# bela_expansion_card_3.net
KiCad netlist of a schematic drawn in Altium Designer
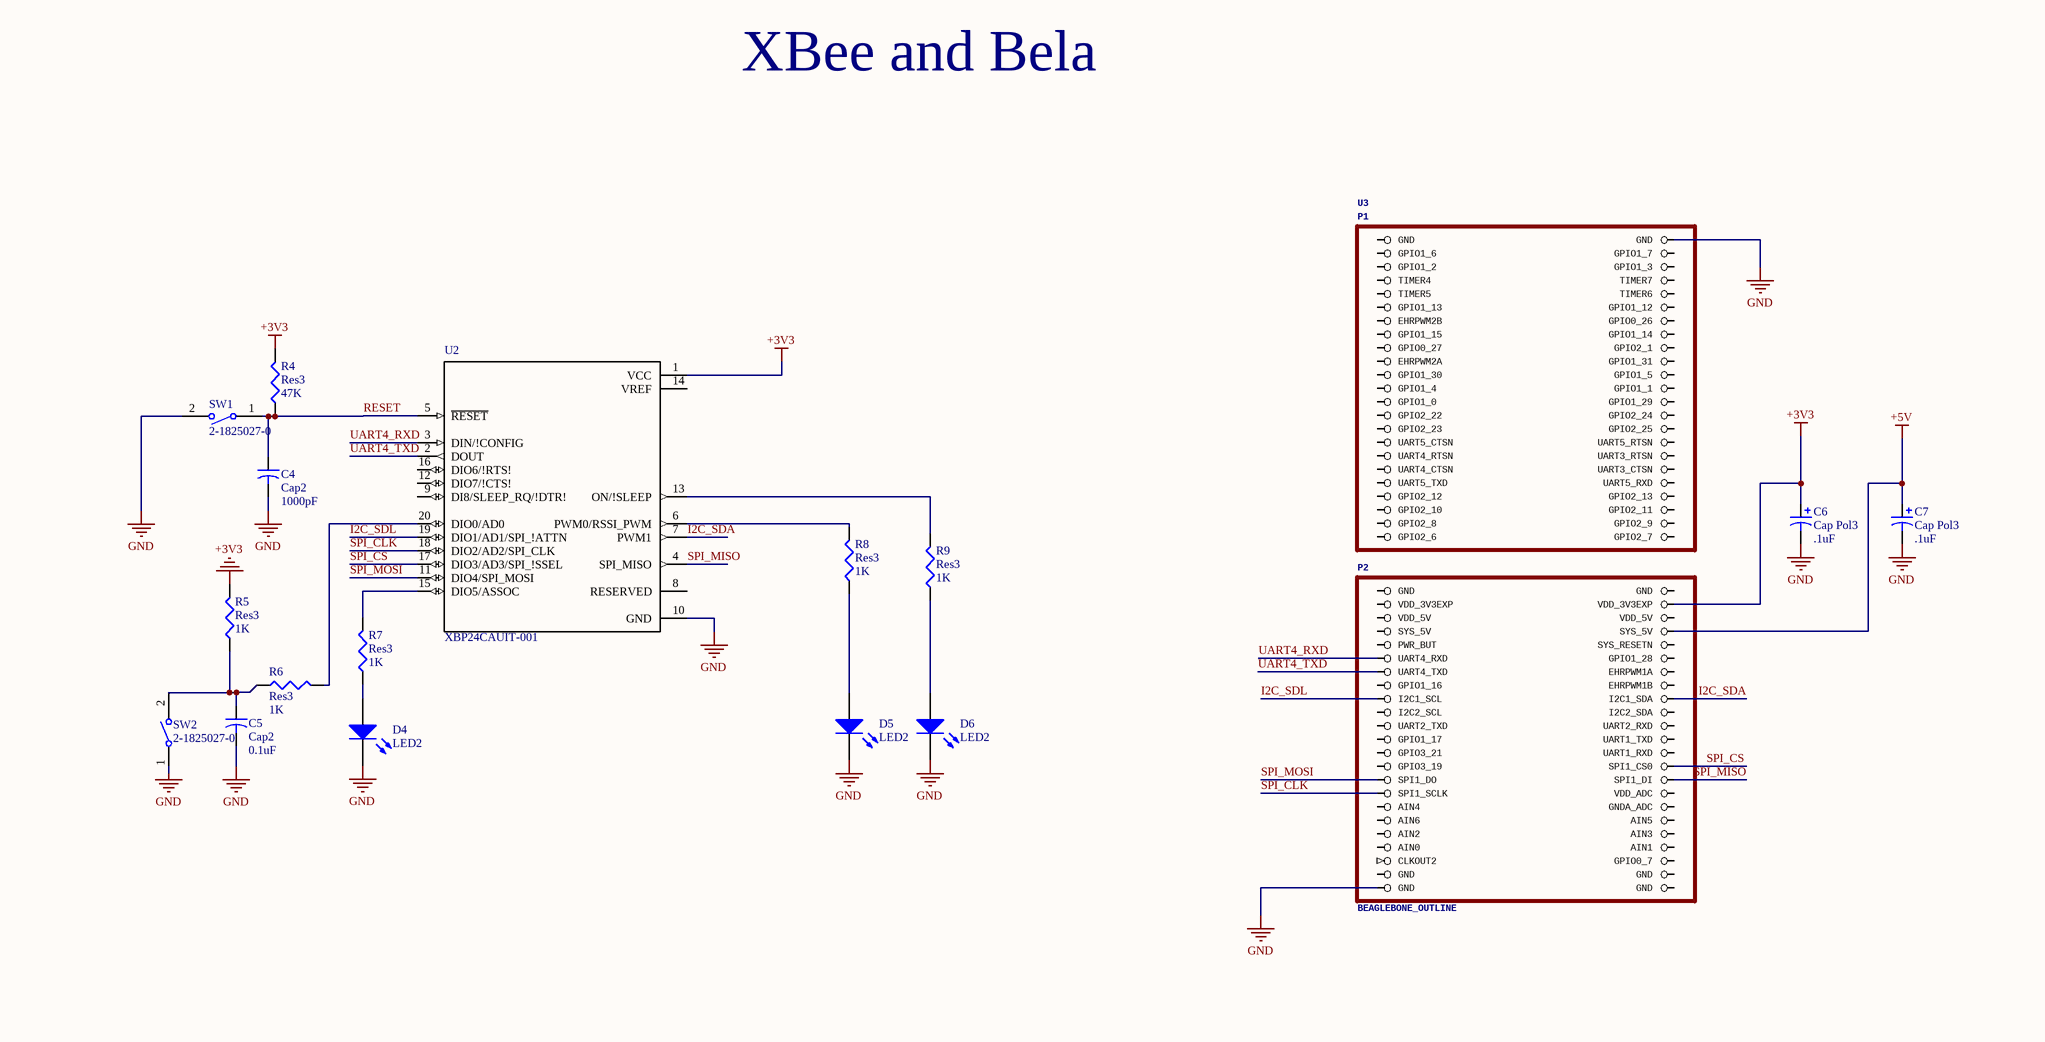
[diagram p0: bela_expansion_card_3.SchDoc]

(export (version "E")
  (design (tool "Eeschema 10.0.6"))
  (components
    (comp (ref "C4")
      (value "Cap2")
      (footprint "C0805")
      (description "Capacitor")
      (fields (field (name "ALTIUM_VALUE") "1000pF") (field (name "PUBLISHER") "Altium Limited"))
      (libsource (lib "EE_Emerge_SkillsProject") (part "Cap2_4"))
    )
    (comp (ref "C5")
      (value "Cap2")
      (footprint "C0805")
      (description "Capacitor")
      (fields (field (name "ALTIUM_VALUE") "0.1uF") (field (name "PUBLISHER") "Altium Limited"))
      (libsource (lib "EE_Emerge_SkillsProject") (part "Cap2_1"))
    )
    (comp (ref "C6")
      (value "Cap Pol3")
      (footprint "C0805")
      (description "Polarized Capacitor (Surface Mount)")
      (fields (field (name "ALTIUM_VALUE") ".1uF") (field (name "PUBLISHER") "Altium Limited"))
      (libsource (lib "Miscellaneous Devices") (part "Cap Pol3"))
    )
    (comp (ref "C7")
      (value "Cap Pol3")
      (footprint "C0805")
      (description "Polarized Capacitor (Surface Mount)")
      (fields (field (name "ALTIUM_VALUE") ".1uF") (field (name "PUBLISHER") "Altium Limited"))
      (libsource (lib "Miscellaneous Devices") (part "Cap Pol3"))
    )
    (comp (ref "D4")
      (value "LED2")
      (footprint "3.2X1.6X1.1")
      (description "Typical RED, GREEN, YELLOW, AMBER GaAs LED")
      (fields (field (name "PUBLISHER") "Altium Limited"))
      (libsource (lib "Miscellaneous Devices") (part "LED2"))
    )
    (comp (ref "D5")
      (value "LED2")
      (footprint "3.2X1.6X1.1")
      (description "Typical RED, GREEN, YELLOW, AMBER GaAs LED")
      (fields (field (name "PUBLISHER") "Altium Limited"))
      (libsource (lib "Miscellaneous Devices") (part "LED2"))
    )
    (comp (ref "D6")
      (value "LED2")
      (footprint "3.2X1.6X1.1")
      (description "Typical RED, GREEN, YELLOW, AMBER GaAs LED")
      (fields (field (name "PUBLISHER") "Altium Limited"))
      (libsource (lib "Miscellaneous Devices") (part "LED2"))
    )
    (comp (ref "R4")
      (value "Res3")
      (footprint "6-0805_L")
      (description "Resistor")
      (fields (field (name "ALTIUM_VALUE") "47K") (field (name "PUBLISHER") "Altium Limited"))
      (libsource (lib "Miscellaneous Devices") (part "Res3"))
    )
    (comp (ref "R5")
      (value "Res3")
      (footprint "6-0805_L")
      (description "Resistor")
      (fields (field (name "ALTIUM_VALUE") "1K") (field (name "PUBLISHER") "Altium Limited"))
      (libsource (lib "Miscellaneous Devices") (part "Res3"))
    )
    (comp (ref "R6")
      (value "Res3")
      (footprint "6-0805_L")
      (description "Resistor")
      (fields (field (name "ALTIUM_VALUE") "1K") (field (name "PUBLISHER") "Altium Limited"))
      (libsource (lib "Miscellaneous Devices") (part "Res3"))
    )
    (comp (ref "R7")
      (value "Res3")
      (footprint "6-0805_L")
      (description "Resistor")
      (fields (field (name "ALTIUM_VALUE") "1K") (field (name "PUBLISHER") "Altium Limited"))
      (libsource (lib "Miscellaneous Devices") (part "Res3"))
    )
    (comp (ref "R8")
      (value "Res3")
      (footprint "6-0805_L")
      (description "Resistor")
      (fields (field (name "ALTIUM_VALUE") "1K") (field (name "PUBLISHER") "Altium Limited"))
      (libsource (lib "Miscellaneous Devices") (part "Res3"))
    )
    (comp (ref "R9")
      (value "Res3")
      (footprint "6-0805_L")
      (description "Resistor")
      (fields (field (name "ALTIUM_VALUE") "1K") (field (name "PUBLISHER") "Altium Limited"))
      (libsource (lib "Miscellaneous Devices") (part "Res3"))
    )
    (comp (ref "SW1")
      (value "2-1825027-0")
      (footprint "DPST-4")
      (description "Micro-Miniature Pushbutton Switch, 50 mA, -35 to 85 degC, 2-Pin THD, RoHS, Bulk")
      (fields (field (name "MANUFACTURER") "TE Connectivity"))
      (libsource (lib "EE_Emerge_SkillsProject") (part "CMP-2000-05529-1"))
    )
    (comp (ref "SW2")
      (value "2-1825027-0")
      (footprint "DPST-4")
      (description "Micro-Miniature Pushbutton Switch, 50 mA, -35 to 85 degC, 2-Pin THD, RoHS, Bulk")
      (fields (field (name "MANUFACTURER") "TE Connectivity"))
      (libsource (lib "EE_Emerge_SkillsProject") (part "CMP-2000-05529-1"))
    )
    (comp (ref "U2")
      (value "XBP24CAUIT-001")
      (footprint "*MODULE_XBP24CAUIT-001")
      (description "802.15.4 Transceiver Module 2.4GHz Antenna Not Included, U.FL Through Hole")
      (fields (field (name "MF") "Digi International"))
      (libsource (lib "XBP24CAUIT-001") (part "XBP24CAUIT-001"))
    )
    (comp (ref "U3")
      (value "BEAGLEBONE_OUTLINE")
      (footprint "BEAGLEBONE_SHIELD")
      (description "Should match A3 pinout - but not completely tested")
      (fields (field (name "P1") "P1") (field (name "P2") "P2"))
      (libsource (lib "adafruit") (part "BEAGLEBONE_OUTLINE"))
    )
  )
  (nets
    (net (code "1") (name "+3V3") (class "Default")
      (node (ref "C6") (pin "1") (pinfunction "1_1") (pintype "passive"))
      (node (ref "R4") (pin "2") (pinfunction "2_2") (pintype "passive"))
      (node (ref "R5") (pin "2") (pinfunction "2_2") (pintype "passive"))
      (node (ref "U2") (pin "1") (pinfunction "VCC_1") (pintype "power_in"))
      (node (ref "U3") (pin "50") (pinfunction "VDD_3V3EXP_50") (pintype "power_in"))
    )
    (net (code "2") (name "+5V") (class "Default")
      (node (ref "C7") (pin "1") (pinfunction "1_1") (pintype "passive"))
      (node (ref "U3") (pin "54") (pinfunction "SYS_5V_54") (pintype "passive"))
    )
    (net (code "3") (name "/I2C_SDA") (class "Default")
      (node (ref "U2") (pin "7") (pinfunction "PWM1_7") (pintype "output"))
      (node (ref "U3") (pin "64") (pinfunction "I2C1_SDA_64") (pintype "passive"))
    )
    (net (code "4") (name "/I2C_SDL") (class "Default")
      (node (ref "U2") (pin "19") (pinfunction "DIO1/AD1/SPI_!ATTN_19") (pintype "bidirectional"))
      (node (ref "U3") (pin "63") (pinfunction "I2C1_SCL_63") (pintype "passive"))
    )
    (net (code "5") (name "/RESET") (class "Default")
      (node (ref "C4") (pin "1") (pinfunction "1_1") (pintype "passive"))
      (node (ref "R4") (pin "1") (pinfunction "1_1") (pintype "passive"))
      (node (ref "SW1") (pin "1") (pinfunction "1_1") (pintype "passive"))
      (node (ref "U2") (pin "5") (pinfunction "~{RESET}_5") (pintype "input"))
    )
    (net (code "6") (name "/SPI_CLK") (class "Default")
      (node (ref "U2") (pin "18") (pinfunction "DIO2/AD2/SPI_CLK_18") (pintype "bidirectional"))
      (node (ref "U3") (pin "77") (pinfunction "SPI1_SCLK_77") (pintype "passive"))
    )
    (net (code "7") (name "/SPI_CS") (class "Default")
      (node (ref "U2") (pin "17") (pinfunction "DIO3/AD3/SPI_!SSEL_17") (pintype "bidirectional"))
      (node (ref "U3") (pin "74") (pinfunction "SPI1_CS0_74") (pintype "passive"))
    )
    (net (code "8") (name "/SPI_MISO") (class "Default")
      (node (ref "U2") (pin "4") (pinfunction "SPI_MISO_4") (pintype "output"))
      (node (ref "U3") (pin "76") (pinfunction "SPI1_DI_76") (pintype "passive"))
    )
    (net (code "9") (name "/SPI_MOSI") (class "Default")
      (node (ref "U2") (pin "11") (pinfunction "DIO4/SPI_MOSI_11") (pintype "bidirectional"))
      (node (ref "U3") (pin "75") (pinfunction "SPI1_DO_75") (pintype "passive"))
    )
    (net (code "10") (name "/UART4_RXD") (class "Default")
      (node (ref "U2") (pin "3") (pinfunction "DIN/!CONFIG_3") (pintype "input"))
      (node (ref "U3") (pin "57") (pinfunction "UART4_RXD_57") (pintype "passive"))
    )
    (net (code "11") (name "/UART4_TXD") (class "Default")
      (node (ref "U2") (pin "2") (pinfunction "DOUT_2") (pintype "output"))
      (node (ref "U3") (pin "59") (pinfunction "UART4_TXD_59") (pintype "passive"))
    )
    (net (code "12") (name "GND") (class "Default")
      (node (ref "C4") (pin "2") (pinfunction "2_2") (pintype "passive"))
      (node (ref "C5") (pin "2") (pinfunction "2_2") (pintype "passive"))
      (node (ref "C6") (pin "2") (pinfunction "2_2") (pintype "passive"))
      (node (ref "C7") (pin "2") (pinfunction "2_2") (pintype "passive"))
      (node (ref "D4") (pin "2") (pinfunction "K_2") (pintype "passive"))
      (node (ref "D5") (pin "2") (pinfunction "K_2") (pintype "passive"))
      (node (ref "D6") (pin "2") (pinfunction "K_2") (pintype "passive"))
      (node (ref "SW1") (pin "2") (pinfunction "2_2") (pintype "passive"))
      (node (ref "SW2") (pin "1") (pinfunction "1_1") (pintype "passive"))
      (node (ref "U2") (pin "10") (pinfunction "GND_10") (pintype "power_in"))
      (node (ref "U3") (pin "2") (pinfunction "GND_2") (pintype "power_in"))
      (node (ref "U3") (pin "91") (pinfunction "GND_91") (pintype "power_in"))
    )
    (net (code "13") (name "Net-(C5-Pad1)") (class "Default")
      (node (ref "C5") (pin "1") (pinfunction "1_1") (pintype "passive"))
      (node (ref "R5") (pin "1") (pinfunction "1_1") (pintype "passive"))
      (node (ref "R6") (pin "1") (pinfunction "1_1") (pintype "passive"))
      (node (ref "SW2") (pin "2") (pinfunction "2_2") (pintype "passive"))
    )
    (net (code "14") (name "Net-(D4-A)") (class "Default")
      (node (ref "D4") (pin "1") (pinfunction "A_1") (pintype "passive"))
      (node (ref "R7") (pin "1") (pinfunction "1_1") (pintype "passive"))
    )
    (net (code "15") (name "Net-(D5-A)") (class "Default")
      (node (ref "D5") (pin "1") (pinfunction "A_1") (pintype "passive"))
      (node (ref "R8") (pin "1") (pinfunction "1_1") (pintype "passive"))
    )
    (net (code "16") (name "Net-(D6-A)") (class "Default")
      (node (ref "D6") (pin "1") (pinfunction "A_1") (pintype "passive"))
      (node (ref "R9") (pin "1") (pinfunction "1_1") (pintype "passive"))
    )
    (net (code "17") (name "Net-(U2-DIO0{slash}AD0)") (class "Default")
      (node (ref "R6") (pin "2") (pinfunction "2_2") (pintype "passive"))
      (node (ref "U2") (pin "20") (pinfunction "DIO0/AD0_20") (pintype "bidirectional"))
    )
    (net (code "18") (name "Net-(U2-DIO5{slash}ASSOC)") (class "Default")
      (node (ref "R7") (pin "2") (pinfunction "2_2") (pintype "passive"))
      (node (ref "U2") (pin "15") (pinfunction "DIO5/ASSOC_15") (pintype "bidirectional"))
    )
    (net (code "19") (name "Net-(U2-ON{slash}!SLEEP)") (class "Default")
      (node (ref "R9") (pin "2") (pinfunction "2_2") (pintype "passive"))
      (node (ref "U2") (pin "13") (pinfunction "ON/!SLEEP_13") (pintype "output"))
    )
    (net (code "20") (name "Net-(U2-PWM0{slash}RSSI_PWM)") (class "Default")
      (node (ref "R8") (pin "2") (pinfunction "2_2") (pintype "passive"))
      (node (ref "U2") (pin "6") (pinfunction "PWM0/RSSI_PWM_6") (pintype "output"))
    )
    (net (code "21") (name "unconnected-(U2-DI8{slash}SLEEP_RQ{slash}!DTR!-Pad9)") (class "Default")
      (node (ref "U2") (pin "9") (pinfunction "DI8/SLEEP_RQ/!DTR!_9") (pintype "bidirectional"))
    )
    (net (code "22") (name "unconnected-(U2-DIO6{slash}!RTS!-Pad16)") (class "Default")
      (node (ref "U2") (pin "16") (pinfunction "DIO6/!RTS!_16") (pintype "bidirectional"))
    )
    (net (code "23") (name "unconnected-(U2-DIO7{slash}!CTS!-Pad12)") (class "Default")
      (node (ref "U2") (pin "12") (pinfunction "DIO7/!CTS!_12") (pintype "bidirectional"))
    )
    (net (code "24") (name "unconnected-(U2-RESERVED-Pad8)") (class "Default")
      (node (ref "U2") (pin "8") (pinfunction "RESERVED_8") (pintype "passive"))
    )
    (net (code "25") (name "unconnected-(U2-VREF-Pad14)") (class "Default")
      (node (ref "U2") (pin "14") (pinfunction "VREF_14") (pintype "power_in"))
    )
    (net (code "26") (name "unconnected-(U3-AIN0-Pad85)") (class "Default")
      (node (ref "U3") (pin "85") (pinfunction "AIN0_85") (pintype "power_in"))
    )
    (net (code "27") (name "unconnected-(U3-AIN1-Pad86)") (class "Default")
      (node (ref "U3") (pin "86") (pinfunction "AIN1_86") (pintype "passive"))
    )
    (net (code "28") (name "unconnected-(U3-AIN2-Pad83)") (class "Default")
      (node (ref "U3") (pin "83") (pinfunction "AIN2_83") (pintype "passive"))
    )
    (net (code "29") (name "unconnected-(U3-AIN3-Pad84)") (class "Default")
      (node (ref "U3") (pin "84") (pinfunction "AIN3_84") (pintype "passive"))
    )
    (net (code "30") (name "unconnected-(U3-AIN4-Pad79)") (class "Default")
      (node (ref "U3") (pin "79") (pinfunction "AIN4_79") (pintype "passive"))
    )
    (net (code "31") (name "unconnected-(U3-AIN5-Pad82)") (class "Default")
      (node (ref "U3") (pin "82") (pinfunction "AIN5_82") (pintype "passive"))
    )
    (net (code "32") (name "unconnected-(U3-AIN6-Pad81)") (class "Default")
      (node (ref "U3") (pin "81") (pinfunction "AIN6_81") (pintype "passive"))
    )
    (net (code "33") (name "unconnected-(U3-CLKOUT2-Pad87)") (class "Default")
      (node (ref "U3") (pin "87") (pinfunction "CLKOUT2_87") (pintype "input"))
    )
    (net (code "34") (name "unconnected-(U3-EHRPWM1A-Pad60)") (class "Default")
      (node (ref "U3") (pin "60") (pinfunction "EHRPWM1A_60") (pintype "passive"))
    )
    (net (code "35") (name "unconnected-(U3-EHRPWM1B-Pad62)") (class "Default")
      (node (ref "U3") (pin "62") (pinfunction "EHRPWM1B_62") (pintype "passive"))
    )
    (net (code "36") (name "unconnected-(U3-EHRPWM2A-Pad19)") (class "Default")
      (node (ref "U3") (pin "19") (pinfunction "EHRPWM2A_19") (pintype "passive"))
    )
    (net (code "37") (name "unconnected-(U3-EHRPWM2B-Pad13)") (class "Default")
      (node (ref "U3") (pin "13") (pinfunction "EHRPWM2B_13") (pintype "passive"))
    )
    (net (code "38") (name "unconnected-(U3-GND-Pad1)") (class "Default")
      (node (ref "U3") (pin "1") (pinfunction "GND_1") (pintype "power_in"))
    )
    (net (code "39") (name "unconnected-(U3-GND-Pad47)") (class "Default")
      (node (ref "U3") (pin "47") (pinfunction "GND_47") (pintype "power_in"))
    )
    (net (code "40") (name "unconnected-(U3-GND-Pad48)") (class "Default")
      (node (ref "U3") (pin "48") (pinfunction "GND_48") (pintype "power_in"))
    )
    (net (code "41") (name "unconnected-(U3-GND-Pad89)") (class "Default")
      (node (ref "U3") (pin "89") (pinfunction "GND_89") (pintype "power_in"))
    )
    (net (code "42") (name "unconnected-(U3-GND-Pad90)") (class "Default")
      (node (ref "U3") (pin "90") (pinfunction "GND_90") (pintype "power_in"))
    )
    (net (code "43") (name "unconnected-(U3-GND-Pad92)") (class "Default")
      (node (ref "U3") (pin "92") (pinfunction "GND_92") (pintype "power_in"))
    )
    (net (code "44") (name "unconnected-(U3-GNDA_ADC-Pad80)") (class "Default")
      (node (ref "U3") (pin "80") (pinfunction "GNDA_ADC_80") (pintype "passive"))
    )
    (net (code "45") (name "unconnected-(U3-GPIO0_7-Pad88)") (class "Default")
      (node (ref "U3") (pin "88") (pinfunction "GPIO0_7_88") (pintype "passive"))
    )
    (net (code "46") (name "unconnected-(U3-GPIO0_26-Pad14)") (class "Default")
      (node (ref "U3") (pin "14") (pinfunction "GPIO0_26_14") (pintype "passive"))
    )
    (net (code "47") (name "unconnected-(U3-GPIO0_27-Pad17)") (class "Default")
      (node (ref "U3") (pin "17") (pinfunction "GPIO0_27_17") (pintype "passive"))
    )
    (net (code "48") (name "unconnected-(U3-GPIO1_0-Pad25)") (class "Default")
      (node (ref "U3") (pin "25") (pinfunction "GPIO1_0_25") (pintype "passive"))
    )
    (net (code "49") (name "unconnected-(U3-GPIO1_1-Pad24)") (class "Default")
      (node (ref "U3") (pin "24") (pinfunction "GPIO1_1_24") (pintype "passive"))
    )
    (net (code "50") (name "unconnected-(U3-GPIO1_2-Pad5)") (class "Default")
      (node (ref "U3") (pin "5") (pinfunction "GPIO1_2_5") (pintype "passive"))
    )
    (net (code "51") (name "unconnected-(U3-GPIO1_3-Pad6)") (class "Default")
      (node (ref "U3") (pin "6") (pinfunction "GPIO1_3_6") (pintype "passive"))
    )
    (net (code "52") (name "unconnected-(U3-GPIO1_4-Pad23)") (class "Default")
      (node (ref "U3") (pin "23") (pinfunction "GPIO1_4_23") (pintype "passive"))
    )
    (net (code "53") (name "unconnected-(U3-GPIO1_5-Pad22)") (class "Default")
      (node (ref "U3") (pin "22") (pinfunction "GPIO1_5_22") (pintype "passive"))
    )
    (net (code "54") (name "unconnected-(U3-GPIO1_6-Pad3)") (class "Default")
      (node (ref "U3") (pin "3") (pinfunction "GPIO1_6_3") (pintype "passive"))
    )
    (net (code "55") (name "unconnected-(U3-GPIO1_7-Pad4)") (class "Default")
      (node (ref "U3") (pin "4") (pinfunction "GPIO1_7_4") (pintype "passive"))
    )
    (net (code "56") (name "unconnected-(U3-GPIO1_12-Pad12)") (class "Default")
      (node (ref "U3") (pin "12") (pinfunction "GPIO1_12_12") (pintype "passive"))
    )
    (net (code "57") (name "unconnected-(U3-GPIO1_13-Pad11)") (class "Default")
      (node (ref "U3") (pin "11") (pinfunction "GPIO1_13_11") (pintype "passive"))
    )
    (net (code "58") (name "unconnected-(U3-GPIO1_14-Pad16)") (class "Default")
      (node (ref "U3") (pin "16") (pinfunction "GPIO1_14_16") (pintype "passive"))
    )
    (net (code "59") (name "unconnected-(U3-GPIO1_15-Pad15)") (class "Default")
      (node (ref "U3") (pin "15") (pinfunction "GPIO1_15_15") (pintype "passive"))
    )
    (net (code "60") (name "unconnected-(U3-GPIO1_16-Pad61)") (class "Default")
      (node (ref "U3") (pin "61") (pinfunction "GPIO1_16_61") (pintype "passive"))
    )
    (net (code "61") (name "unconnected-(U3-GPIO1_17-Pad69)") (class "Default")
      (node (ref "U3") (pin "69") (pinfunction "GPIO1_17_69") (pintype "passive"))
    )
    (net (code "62") (name "unconnected-(U3-GPIO1_28-Pad58)") (class "Default")
      (node (ref "U3") (pin "58") (pinfunction "GPIO1_28_58") (pintype "passive"))
    )
    (net (code "63") (name "unconnected-(U3-GPIO1_29-Pad26)") (class "Default")
      (node (ref "U3") (pin "26") (pinfunction "GPIO1_29_26") (pintype "passive"))
    )
    (net (code "64") (name "unconnected-(U3-GPIO1_30-Pad21)") (class "Default")
      (node (ref "U3") (pin "21") (pinfunction "GPIO1_30_21") (pintype "passive"))
    )
    (net (code "65") (name "unconnected-(U3-GPIO1_31-Pad20)") (class "Default")
      (node (ref "U3") (pin "20") (pinfunction "GPIO1_31_20") (pintype "passive"))
    )
    (net (code "66") (name "unconnected-(U3-GPIO2_1-Pad18)") (class "Default")
      (node (ref "U3") (pin "18") (pinfunction "GPIO2_1_18") (pintype "passive"))
    )
    (net (code "67") (name "unconnected-(U3-GPIO2_6-Pad45)") (class "Default")
      (node (ref "U3") (pin "45") (pinfunction "GPIO2_6_45") (pintype "passive"))
    )
    (net (code "68") (name "unconnected-(U3-GPIO2_7-Pad46)") (class "Default")
      (node (ref "U3") (pin "46") (pinfunction "GPIO2_7_46") (pintype "passive"))
    )
    (net (code "69") (name "unconnected-(U3-GPIO2_8-Pad43)") (class "Default")
      (node (ref "U3") (pin "43") (pinfunction "GPIO2_8_43") (pintype "passive"))
    )
    (net (code "70") (name "unconnected-(U3-GPIO2_9-Pad44)") (class "Default")
      (node (ref "U3") (pin "44") (pinfunction "GPIO2_9_44") (pintype "passive"))
    )
    (net (code "71") (name "unconnected-(U3-GPIO2_10-Pad41)") (class "Default")
      (node (ref "U3") (pin "41") (pinfunction "GPIO2_10_41") (pintype "passive"))
    )
    (net (code "72") (name "unconnected-(U3-GPIO2_11-Pad42)") (class "Default")
      (node (ref "U3") (pin "42") (pinfunction "GPIO2_11_42") (pintype "passive"))
    )
    (net (code "73") (name "unconnected-(U3-GPIO2_12-Pad39)") (class "Default")
      (node (ref "U3") (pin "39") (pinfunction "GPIO2_12_39") (pintype "passive"))
    )
    (net (code "74") (name "unconnected-(U3-GPIO2_13-Pad40)") (class "Default")
      (node (ref "U3") (pin "40") (pinfunction "GPIO2_13_40") (pintype "passive"))
    )
    (net (code "75") (name "unconnected-(U3-GPIO2_22-Pad27)") (class "Default")
      (node (ref "U3") (pin "27") (pinfunction "GPIO2_22_27") (pintype "passive"))
    )
    (net (code "76") (name "unconnected-(U3-GPIO2_23-Pad29)") (class "Default")
      (node (ref "U3") (pin "29") (pinfunction "GPIO2_23_29") (pintype "passive"))
    )
    (net (code "77") (name "unconnected-(U3-GPIO2_24-Pad28)") (class "Default")
      (node (ref "U3") (pin "28") (pinfunction "GPIO2_24_28") (pintype "passive"))
    )
    (net (code "78") (name "unconnected-(U3-GPIO2_25-Pad30)") (class "Default")
      (node (ref "U3") (pin "30") (pinfunction "GPIO2_25_30") (pintype "passive"))
    )
    (net (code "79") (name "unconnected-(U3-GPIO3_19-Pad73)") (class "Default")
      (node (ref "U3") (pin "73") (pinfunction "GPIO3_19_73") (pintype "passive"))
    )
    (net (code "80") (name "unconnected-(U3-GPIO3_21-Pad71)") (class "Default")
      (node (ref "U3") (pin "71") (pinfunction "GPIO3_21_71") (pintype "passive"))
    )
    (net (code "81") (name "unconnected-(U3-I2C2_SCL-Pad65)") (class "Default")
      (node (ref "U3") (pin "65") (pinfunction "I2C2_SCL_65") (pintype "passive"))
    )
    (net (code "82") (name "unconnected-(U3-I2C2_SDA-Pad66)") (class "Default")
      (node (ref "U3") (pin "66") (pinfunction "I2C2_SDA_66") (pintype "passive"))
    )
    (net (code "83") (name "unconnected-(U3-PWR_BUT-Pad55)") (class "Default")
      (node (ref "U3") (pin "55") (pinfunction "PWR_BUT_55") (pintype "passive"))
    )
    (net (code "84") (name "unconnected-(U3-SYS_5V-Pad53)") (class "Default")
      (node (ref "U3") (pin "53") (pinfunction "SYS_5V_53") (pintype "power_in"))
    )
    (net (code "85") (name "unconnected-(U3-SYS_RESETN-Pad56)") (class "Default")
      (node (ref "U3") (pin "56") (pinfunction "SYS_RESETN_56") (pintype "passive"))
    )
    (net (code "86") (name "unconnected-(U3-TIMER4-Pad7)") (class "Default")
      (node (ref "U3") (pin "7") (pinfunction "TIMER4_7") (pintype "passive"))
    )
    (net (code "87") (name "unconnected-(U3-TIMER5-Pad9)") (class "Default")
      (node (ref "U3") (pin "9") (pinfunction "TIMER5_9") (pintype "passive"))
    )
    (net (code "88") (name "unconnected-(U3-TIMER6-Pad10)") (class "Default")
      (node (ref "U3") (pin "10") (pinfunction "TIMER6_10") (pintype "passive"))
    )
    (net (code "89") (name "unconnected-(U3-TIMER7-Pad8)") (class "Default")
      (node (ref "U3") (pin "8") (pinfunction "TIMER7_8") (pintype "passive"))
    )
    (net (code "90") (name "unconnected-(U3-UART1_RXD-Pad72)") (class "Default")
      (node (ref "U3") (pin "72") (pinfunction "UART1_RXD_72") (pintype "passive"))
    )
    (net (code "91") (name "unconnected-(U3-UART1_TXD-Pad70)") (class "Default")
      (node (ref "U3") (pin "70") (pinfunction "UART1_TXD_70") (pintype "passive"))
    )
    (net (code "92") (name "unconnected-(U3-UART2_RXD-Pad68)") (class "Default")
      (node (ref "U3") (pin "68") (pinfunction "UART2_RXD_68") (pintype "passive"))
    )
    (net (code "93") (name "unconnected-(U3-UART2_TXD-Pad67)") (class "Default")
      (node (ref "U3") (pin "67") (pinfunction "UART2_TXD_67") (pintype "passive"))
    )
    (net (code "94") (name "unconnected-(U3-UART3_CTSN-Pad36)") (class "Default")
      (node (ref "U3") (pin "36") (pinfunction "UART3_CTSN_36") (pintype "passive"))
    )
    (net (code "95") (name "unconnected-(U3-UART3_RTSN-Pad34)") (class "Default")
      (node (ref "U3") (pin "34") (pinfunction "UART3_RTSN_34") (pintype "passive"))
    )
    (net (code "96") (name "unconnected-(U3-UART4_CTSN-Pad35)") (class "Default")
      (node (ref "U3") (pin "35") (pinfunction "UART4_CTSN_35") (pintype "passive"))
    )
    (net (code "97") (name "unconnected-(U3-UART4_RTSN-Pad33)") (class "Default")
      (node (ref "U3") (pin "33") (pinfunction "UART4_RTSN_33") (pintype "passive"))
    )
    (net (code "98") (name "unconnected-(U3-UART5_CTSN-Pad31)") (class "Default")
      (node (ref "U3") (pin "31") (pinfunction "UART5_CTSN_31") (pintype "passive"))
    )
    (net (code "99") (name "unconnected-(U3-UART5_RTSN-Pad32)") (class "Default")
      (node (ref "U3") (pin "32") (pinfunction "UART5_RTSN_32") (pintype "passive"))
    )
    (net (code "100") (name "unconnected-(U3-UART5_RXD-Pad38)") (class "Default")
      (node (ref "U3") (pin "38") (pinfunction "UART5_RXD_38") (pintype "passive"))
    )
    (net (code "101") (name "unconnected-(U3-UART5_TXD-Pad37)") (class "Default")
      (node (ref "U3") (pin "37") (pinfunction "UART5_TXD_37") (pintype "passive"))
    )
    (net (code "102") (name "unconnected-(U3-VDD_3V3EXP-Pad49)") (class "Default")
      (node (ref "U3") (pin "49") (pinfunction "VDD_3V3EXP_49") (pintype "power_in"))
    )
    (net (code "103") (name "unconnected-(U3-VDD_5V-Pad51)") (class "Default")
      (node (ref "U3") (pin "51") (pinfunction "VDD_5V_51") (pintype "power_in"))
    )
    (net (code "104") (name "unconnected-(U3-VDD_5V-Pad52)") (class "Default")
      (node (ref "U3") (pin "52") (pinfunction "VDD_5V_52") (pintype "power_in"))
    )
    (net (code "105") (name "unconnected-(U3-VDD_ADC-Pad78)") (class "Default")
      (node (ref "U3") (pin "78") (pinfunction "VDD_ADC_78") (pintype "passive"))
    )
  )
)
